# nguon.net
KiCad netlist of a schematic drawn in Altium Designer
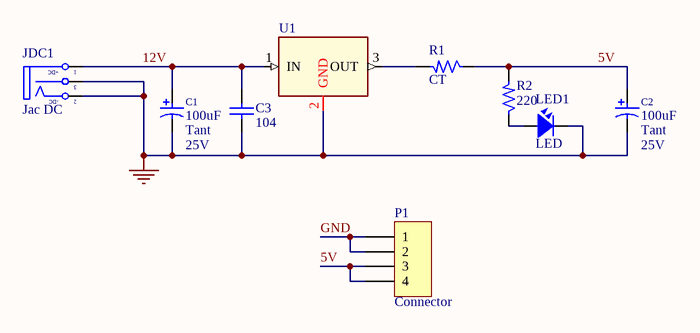
[diagram p0: nguon.SchDoc]

(export (version "E")
  (design (tool "Eeschema 10.0.6"))
  (components
    (comp (ref "C1")
      (value "100uF")
      (footprint "RADIAL B")
      (description "Polarized Capacitor")
      (fields
        (field (name "MANUFACTURER") "FARNELL")
        (field (name "CAPACITOR TYPE") "Tant")
        (field (name "VOLT") "25V")
        (field (name "PUBLISHER") "Hoang Nguyen")
      )
      (libsource (lib "hphonglib") (part "Cap_Pol"))
    )
    (comp (ref "C2")
      (value "100uF")
      (footprint "RADIAL B")
      (description "Polarized Capacitor")
      (fields
        (field (name "MANUFACTURER") "FARNELL")
        (field (name "CAPACITOR TYPE") "Tant")
        (field (name "VOLT") "25V")
        (field (name "PUBLISHER") "Hoang Nguyen")
      )
      (libsource (lib "hphonglib") (part "Cap_Pol"))
    )
    (comp (ref "C3")
      (value "104")
      (footprint "Tu-pico")
      (description "Capacitor")
      (fields (field (name "Comment") "Capacitor Ceramic") (field (name "PUBLISHER") "Altium Limited"))
      (libsource (lib "My Library") (part "CapCeramic"))
    )
    (comp (ref "JDC1")
      (value "Jac DC")
      (footprint "DC0")
      (description "Jac DC input")
      (libsource (lib "Library") (part "DCIN"))
    )
    (comp (ref "LED1")
      (value "LED")
      (footprint "LED-5-RED")
      (description "LED Single colour Green and Red")
      (libsource (lib "syhaunguyen") (part "LED"))
    )
    (comp (ref "P1")
      (value "Connector")
      (footprint "MinhTien_PCBLib:JST-XH_B4B-XH-A")
      (libsource (lib "MinhTien_SCHLib") (part "Connector_4pin"))
    )
    (comp (ref "R1")
      (value "CT")
      (footprint "R1/8W")
      (description "Resistor 1/4W")
      (libsource (lib "My Library") (part "R"))
    )
    (comp (ref "R2")
      (value "220")
      (footprint "R1/8W")
      (description "Resistor 1/4W")
      (libsource (lib "My Library") (part "R"))
    )
    (comp (ref "U1")
      (value "LM78xx")
      (footprint "TO-220")
      (description "Regulator")
      (fields
        (field (name "MANUFACTURER") "Fairchild Semiconductor Corporation")
        (field (name "TOLERANCE") "4 %")
        (field (name "PUBLISHER") "Hoang Nguyen")
      )
      (libsource (lib "hphonglib") (part "LM78xx"))
    )
  )
  (nets
    (net (code "1") (name "/5V") (class "Default")
      (node (ref "C2") (pin "1") (pinfunction "1_1") (pintype "passive"))
      (node (ref "P1") (pin "3") (pinfunction "3_3") (pintype "passive"))
      (node (ref "P1") (pin "4") (pinfunction "4_4") (pintype "passive"))
      (node (ref "R1") (pin "1") (pinfunction "1_1") (pintype "passive"))
      (node (ref "R2") (pin "2") (pinfunction "2_2") (pintype "passive"))
    )
    (net (code "2") (name "/12V") (class "Default")
      (node (ref "C1") (pin "1") (pinfunction "1_1") (pintype "passive"))
      (node (ref "C3") (pin "2") (pinfunction "2_2") (pintype "passive"))
      (node (ref "JDC1") (pin "1") (pinfunction "T_1") (pintype "passive"))
      (node (ref "U1") (pin "1") (pinfunction "IN_1") (pintype "input"))
    )
    (net (code "3") (name "GND") (class "Default")
      (node (ref "C1") (pin "2") (pinfunction "2_2") (pintype "passive"))
      (node (ref "C2") (pin "2") (pinfunction "2_2") (pintype "passive"))
      (node (ref "C3") (pin "1") (pinfunction "1_1") (pintype "passive"))
      (node (ref "JDC1") (pin "2") (pinfunction "TN_2") (pintype "passive"))
      (node (ref "JDC1") (pin "3") (pinfunction "S_3") (pintype "power_in"))
      (node (ref "LED1") (pin "2") (pinfunction "2_2") (pintype "passive"))
      (node (ref "P1") (pin "1") (pinfunction "1_1") (pintype "passive"))
      (node (ref "P1") (pin "2") (pinfunction "2_2") (pintype "passive"))
      (node (ref "U1") (pin "2") (pinfunction "GND_2") (pintype "power_in"))
    )
    (net (code "4") (name "Net-(LED1-Pad1)") (class "Default")
      (node (ref "LED1") (pin "1") (pinfunction "1_1") (pintype "passive"))
      (node (ref "R2") (pin "1") (pinfunction "1_1") (pintype "passive"))
    )
    (net (code "5") (name "Net-(U1-OUT)") (class "Default")
      (node (ref "R1") (pin "2") (pinfunction "2_2") (pintype "passive"))
      (node (ref "U1") (pin "3") (pinfunction "OUT_3") (pintype "output"))
    )
  )
)
